# LineFollowerSensor.net
KiCad netlist of a schematic drawn in Altium Designer
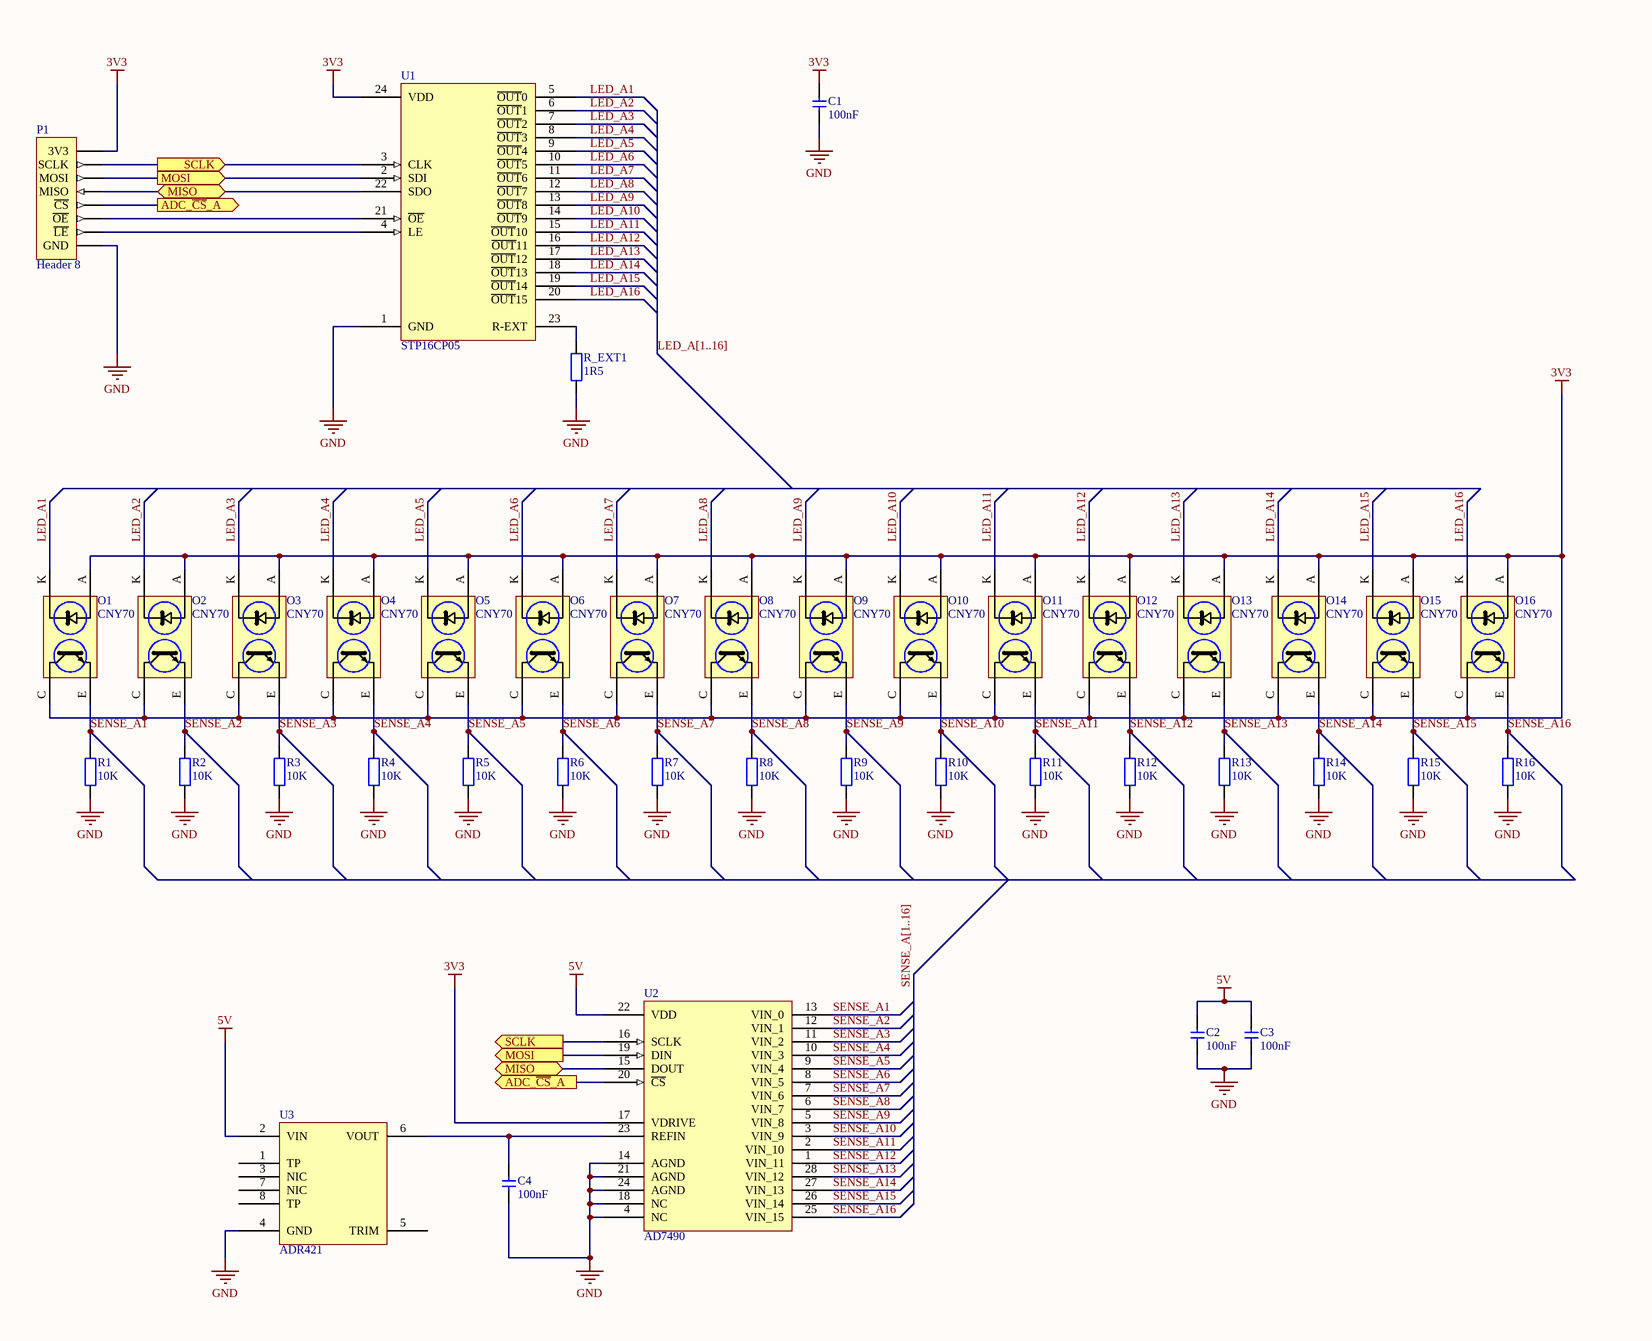
[diagram p0: LineFollowerSensor.SchDoc, left]
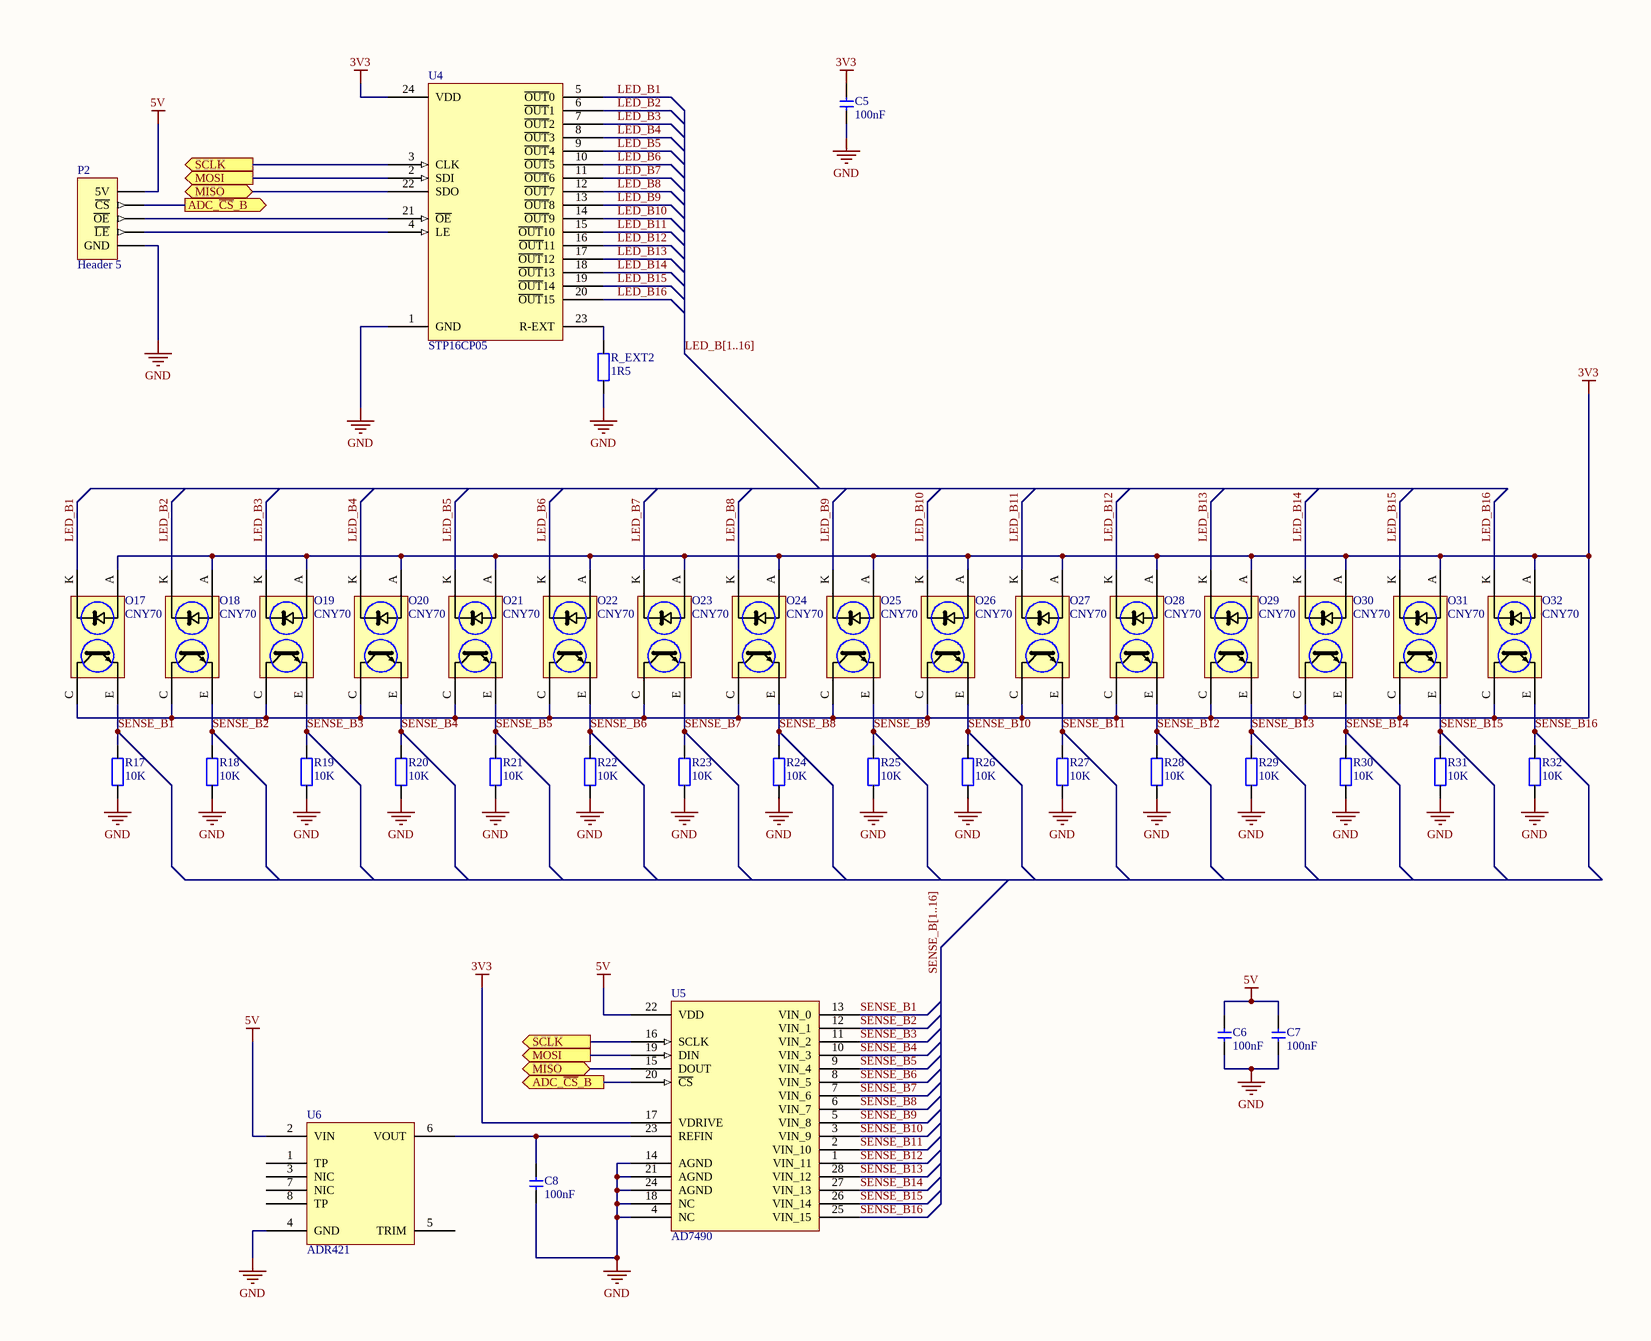
[diagram p1: LineFollowerSensor.SchDoc, right]

(export (version "E")
  (design (tool "Eeschema 10.0.6"))
  (components
    (comp (ref "C1")
      (value "100nF")
      (footprint "FP_0805_CAP_085")
      (description "YAGEO Ceramic Capacitor")
      (fields (field (name "VOLTAGE") "50") (field (name "TOLERANCE") "10%"))
      (libsource (lib "RET0805_RES-CAP_lib") (part "CAP_100nF"))
    )
    (comp (ref "C2")
      (value "100nF")
      (footprint "FP_0805_CAP_085")
      (description "YAGEO Ceramic Capacitor")
      (fields (field (name "VOLTAGE") "50") (field (name "TOLERANCE") "10%"))
      (libsource (lib "RET0805_RES-CAP_lib") (part "CAP_100nF"))
    )
    (comp (ref "C3")
      (value "100nF")
      (footprint "FP_0805_CAP_085")
      (description "YAGEO Ceramic Capacitor")
      (fields (field (name "VOLTAGE") "50") (field (name "TOLERANCE") "10%"))
      (libsource (lib "RET0805_RES-CAP_lib") (part "CAP_100nF"))
    )
    (comp (ref "C4")
      (value "100nF")
      (footprint "FP_0805_CAP_085")
      (description "YAGEO Ceramic Capacitor")
      (fields (field (name "VOLTAGE") "50") (field (name "TOLERANCE") "10%"))
      (libsource (lib "RET0805_RES-CAP_lib") (part "CAP_100nF"))
    )
    (comp (ref "C5")
      (value "100nF")
      (footprint "FP_0805_CAP_085")
      (description "YAGEO Ceramic Capacitor")
      (fields (field (name "VOLTAGE") "50") (field (name "TOLERANCE") "10%"))
      (libsource (lib "RET0805_RES-CAP_lib") (part "CAP_100nF"))
    )
    (comp (ref "C6")
      (value "100nF")
      (footprint "FP_0805_CAP_085")
      (description "YAGEO Ceramic Capacitor")
      (fields (field (name "VOLTAGE") "50") (field (name "TOLERANCE") "10%"))
      (libsource (lib "RET0805_RES-CAP_lib") (part "CAP_100nF"))
    )
    (comp (ref "C7")
      (value "100nF")
      (footprint "FP_0805_CAP_085")
      (description "YAGEO Ceramic Capacitor")
      (fields (field (name "VOLTAGE") "50") (field (name "TOLERANCE") "10%"))
      (libsource (lib "RET0805_RES-CAP_lib") (part "CAP_100nF"))
    )
    (comp (ref "C8")
      (value "100nF")
      (footprint "FP_0805_CAP_085")
      (description "YAGEO Ceramic Capacitor")
      (fields (field (name "VOLTAGE") "50") (field (name "TOLERANCE") "10%"))
      (libsource (lib "RET0805_RES-CAP_lib") (part "CAP_100nF"))
    )
    (comp (ref "O1")
      (value "CNY70")
      (footprint "FP_CNY70")
      (description "Optoérzékelő, CNY70")
      (libsource (lib "hallglib") (part "CNY70"))
    )
    (comp (ref "O2")
      (value "CNY70")
      (footprint "FP_CNY70")
      (description "Optoérzékelő, CNY70")
      (libsource (lib "hallglib") (part "CNY70"))
    )
    (comp (ref "O3")
      (value "CNY70")
      (footprint "FP_CNY70")
      (description "Optoérzékelő, CNY70")
      (libsource (lib "hallglib") (part "CNY70"))
    )
    (comp (ref "O4")
      (value "CNY70")
      (footprint "FP_CNY70")
      (description "Optoérzékelő, CNY70")
      (libsource (lib "hallglib") (part "CNY70"))
    )
    (comp (ref "O5")
      (value "CNY70")
      (footprint "FP_CNY70")
      (description "Optoérzékelő, CNY70")
      (libsource (lib "hallglib") (part "CNY70"))
    )
    (comp (ref "O6")
      (value "CNY70")
      (footprint "FP_CNY70")
      (description "Optoérzékelő, CNY70")
      (libsource (lib "hallglib") (part "CNY70"))
    )
    (comp (ref "O7")
      (value "CNY70")
      (footprint "FP_CNY70")
      (description "Optoérzékelő, CNY70")
      (libsource (lib "hallglib") (part "CNY70"))
    )
    (comp (ref "O8")
      (value "CNY70")
      (footprint "FP_CNY70")
      (description "Optoérzékelő, CNY70")
      (libsource (lib "hallglib") (part "CNY70"))
    )
    (comp (ref "O9")
      (value "CNY70")
      (footprint "FP_CNY70")
      (description "Optoérzékelő, CNY70")
      (libsource (lib "hallglib") (part "CNY70"))
    )
    (comp (ref "O10")
      (value "CNY70")
      (footprint "FP_CNY70")
      (description "Optoérzékelő, CNY70")
      (libsource (lib "hallglib") (part "CNY70"))
    )
    (comp (ref "O11")
      (value "CNY70")
      (footprint "FP_CNY70")
      (description "Optoérzékelő, CNY70")
      (libsource (lib "hallglib") (part "CNY70"))
    )
    (comp (ref "O12")
      (value "CNY70")
      (footprint "FP_CNY70")
      (description "Optoérzékelő, CNY70")
      (libsource (lib "hallglib") (part "CNY70"))
    )
    (comp (ref "O13")
      (value "CNY70")
      (footprint "FP_CNY70")
      (description "Optoérzékelő, CNY70")
      (libsource (lib "hallglib") (part "CNY70"))
    )
    (comp (ref "O14")
      (value "CNY70")
      (footprint "FP_CNY70")
      (description "Optoérzékelő, CNY70")
      (libsource (lib "hallglib") (part "CNY70"))
    )
    (comp (ref "O15")
      (value "CNY70")
      (footprint "FP_CNY70")
      (description "Optoérzékelő, CNY70")
      (libsource (lib "hallglib") (part "CNY70"))
    )
    (comp (ref "O16")
      (value "CNY70")
      (footprint "FP_CNY70")
      (description "Optoérzékelő, CNY70")
      (libsource (lib "hallglib") (part "CNY70"))
    )
    (comp (ref "O17")
      (value "CNY70")
      (footprint "FP_CNY70")
      (description "Optoérzékelő, CNY70")
      (libsource (lib "hallglib") (part "CNY70"))
    )
    (comp (ref "O18")
      (value "CNY70")
      (footprint "FP_CNY70")
      (description "Optoérzékelő, CNY70")
      (libsource (lib "hallglib") (part "CNY70"))
    )
    (comp (ref "O19")
      (value "CNY70")
      (footprint "FP_CNY70")
      (description "Optoérzékelő, CNY70")
      (libsource (lib "hallglib") (part "CNY70"))
    )
    (comp (ref "O20")
      (value "CNY70")
      (footprint "FP_CNY70")
      (description "Optoérzékelő, CNY70")
      (libsource (lib "hallglib") (part "CNY70"))
    )
    (comp (ref "O21")
      (value "CNY70")
      (footprint "FP_CNY70")
      (description "Optoérzékelő, CNY70")
      (libsource (lib "hallglib") (part "CNY70"))
    )
    (comp (ref "O22")
      (value "CNY70")
      (footprint "FP_CNY70")
      (description "Optoérzékelő, CNY70")
      (libsource (lib "hallglib") (part "CNY70"))
    )
    (comp (ref "O23")
      (value "CNY70")
      (footprint "FP_CNY70")
      (description "Optoérzékelő, CNY70")
      (libsource (lib "hallglib") (part "CNY70"))
    )
    (comp (ref "O24")
      (value "CNY70")
      (footprint "FP_CNY70")
      (description "Optoérzékelő, CNY70")
      (libsource (lib "hallglib") (part "CNY70"))
    )
    (comp (ref "O25")
      (value "CNY70")
      (footprint "FP_CNY70")
      (description "Optoérzékelő, CNY70")
      (libsource (lib "hallglib") (part "CNY70"))
    )
    (comp (ref "O26")
      (value "CNY70")
      (footprint "FP_CNY70")
      (description "Optoérzékelő, CNY70")
      (libsource (lib "hallglib") (part "CNY70"))
    )
    (comp (ref "O27")
      (value "CNY70")
      (footprint "FP_CNY70")
      (description "Optoérzékelő, CNY70")
      (libsource (lib "hallglib") (part "CNY70"))
    )
    (comp (ref "O28")
      (value "CNY70")
      (footprint "FP_CNY70")
      (description "Optoérzékelő, CNY70")
      (libsource (lib "hallglib") (part "CNY70"))
    )
    (comp (ref "O29")
      (value "CNY70")
      (footprint "FP_CNY70")
      (description "Optoérzékelő, CNY70")
      (libsource (lib "hallglib") (part "CNY70"))
    )
    (comp (ref "O30")
      (value "CNY70")
      (footprint "FP_CNY70")
      (description "Optoérzékelő, CNY70")
      (libsource (lib "hallglib") (part "CNY70"))
    )
    (comp (ref "O31")
      (value "CNY70")
      (footprint "FP_CNY70")
      (description "Optoérzékelő, CNY70")
      (libsource (lib "hallglib") (part "CNY70"))
    )
    (comp (ref "O32")
      (value "CNY70")
      (footprint "FP_CNY70")
      (description "Optoérzékelő, CNY70")
      (libsource (lib "hallglib") (part "CNY70"))
    )
    (comp (ref "P1")
      (value "Header 8")
      (footprint "HDR1X8")
      (description "Header, 8-Pin")
      (fields (field (name "PUBLISHER") "Altium Limited"))
      (libsource (lib "Miscellaneous Connectors") (part "Header 8"))
    )
    (comp (ref "P2")
      (value "Header 5")
      (footprint "HDR1X5")
      (description "Header, 5-Pin")
      (fields (field (name "PUBLISHER") "Altium Limited"))
      (libsource (lib "Miscellaneous Connectors") (part "Header 5"))
    )
    (comp (ref "R1")
      (value "10K")
      (footprint "FP_0805_RES")
      (description "YAGEO SMD RESISTOR")
      (fields (field (name "POWER") "125 mW") (field (name "TOLERANCE") "1%"))
      (libsource (lib "RET0805_RES-CAP_lib") (part "RES_10K"))
    )
    (comp (ref "R2")
      (value "10K")
      (footprint "FP_0805_RES")
      (description "YAGEO SMD RESISTOR")
      (fields (field (name "POWER") "125 mW") (field (name "TOLERANCE") "1%"))
      (libsource (lib "RET0805_RES-CAP_lib") (part "RES_10K"))
    )
    (comp (ref "R3")
      (value "10K")
      (footprint "FP_0805_RES")
      (description "YAGEO SMD RESISTOR")
      (fields (field (name "POWER") "125 mW") (field (name "TOLERANCE") "1%"))
      (libsource (lib "RET0805_RES-CAP_lib") (part "RES_10K"))
    )
    (comp (ref "R4")
      (value "10K")
      (footprint "FP_0805_RES")
      (description "YAGEO SMD RESISTOR")
      (fields (field (name "POWER") "125 mW") (field (name "TOLERANCE") "1%"))
      (libsource (lib "RET0805_RES-CAP_lib") (part "RES_10K"))
    )
    (comp (ref "R5")
      (value "10K")
      (footprint "FP_0805_RES")
      (description "YAGEO SMD RESISTOR")
      (fields (field (name "POWER") "125 mW") (field (name "TOLERANCE") "1%"))
      (libsource (lib "RET0805_RES-CAP_lib") (part "RES_10K"))
    )
    (comp (ref "R6")
      (value "10K")
      (footprint "FP_0805_RES")
      (description "YAGEO SMD RESISTOR")
      (fields (field (name "POWER") "125 mW") (field (name "TOLERANCE") "1%"))
      (libsource (lib "RET0805_RES-CAP_lib") (part "RES_10K"))
    )
    (comp (ref "R7")
      (value "10K")
      (footprint "FP_0805_RES")
      (description "YAGEO SMD RESISTOR")
      (fields (field (name "POWER") "125 mW") (field (name "TOLERANCE") "1%"))
      (libsource (lib "RET0805_RES-CAP_lib") (part "RES_10K"))
    )
    (comp (ref "R8")
      (value "10K")
      (footprint "FP_0805_RES")
      (description "YAGEO SMD RESISTOR")
      (fields (field (name "POWER") "125 mW") (field (name "TOLERANCE") "1%"))
      (libsource (lib "RET0805_RES-CAP_lib") (part "RES_10K"))
    )
    (comp (ref "R9")
      (value "10K")
      (footprint "FP_0805_RES")
      (description "YAGEO SMD RESISTOR")
      (fields (field (name "POWER") "125 mW") (field (name "TOLERANCE") "1%"))
      (libsource (lib "RET0805_RES-CAP_lib") (part "RES_10K"))
    )
    (comp (ref "R10")
      (value "10K")
      (footprint "FP_0805_RES")
      (description "YAGEO SMD RESISTOR")
      (fields (field (name "POWER") "125 mW") (field (name "TOLERANCE") "1%"))
      (libsource (lib "RET0805_RES-CAP_lib") (part "RES_10K"))
    )
    (comp (ref "R11")
      (value "10K")
      (footprint "FP_0805_RES")
      (description "YAGEO SMD RESISTOR")
      (fields (field (name "POWER") "125 mW") (field (name "TOLERANCE") "1%"))
      (libsource (lib "RET0805_RES-CAP_lib") (part "RES_10K"))
    )
    (comp (ref "R12")
      (value "10K")
      (footprint "FP_0805_RES")
      (description "YAGEO SMD RESISTOR")
      (fields (field (name "POWER") "125 mW") (field (name "TOLERANCE") "1%"))
      (libsource (lib "RET0805_RES-CAP_lib") (part "RES_10K"))
    )
    (comp (ref "R13")
      (value "10K")
      (footprint "FP_0805_RES")
      (description "YAGEO SMD RESISTOR")
      (fields (field (name "POWER") "125 mW") (field (name "TOLERANCE") "1%"))
      (libsource (lib "RET0805_RES-CAP_lib") (part "RES_10K"))
    )
    (comp (ref "R14")
      (value "10K")
      (footprint "FP_0805_RES")
      (description "YAGEO SMD RESISTOR")
      (fields (field (name "POWER") "125 mW") (field (name "TOLERANCE") "1%"))
      (libsource (lib "RET0805_RES-CAP_lib") (part "RES_10K"))
    )
    (comp (ref "R15")
      (value "10K")
      (footprint "FP_0805_RES")
      (description "YAGEO SMD RESISTOR")
      (fields (field (name "POWER") "125 mW") (field (name "TOLERANCE") "1%"))
      (libsource (lib "RET0805_RES-CAP_lib") (part "RES_10K"))
    )
    (comp (ref "R16")
      (value "10K")
      (footprint "FP_0805_RES")
      (description "YAGEO SMD RESISTOR")
      (fields (field (name "POWER") "125 mW") (field (name "TOLERANCE") "1%"))
      (libsource (lib "RET0805_RES-CAP_lib") (part "RES_10K"))
    )
    (comp (ref "R17")
      (value "10K")
      (footprint "FP_0805_RES")
      (description "YAGEO SMD RESISTOR")
      (fields (field (name "POWER") "125 mW") (field (name "TOLERANCE") "1%"))
      (libsource (lib "RET0805_RES-CAP_lib") (part "RES_10K"))
    )
    (comp (ref "R18")
      (value "10K")
      (footprint "FP_0805_RES")
      (description "YAGEO SMD RESISTOR")
      (fields (field (name "POWER") "125 mW") (field (name "TOLERANCE") "1%"))
      (libsource (lib "RET0805_RES-CAP_lib") (part "RES_10K"))
    )
    (comp (ref "R19")
      (value "10K")
      (footprint "FP_0805_RES")
      (description "YAGEO SMD RESISTOR")
      (fields (field (name "POWER") "125 mW") (field (name "TOLERANCE") "1%"))
      (libsource (lib "RET0805_RES-CAP_lib") (part "RES_10K"))
    )
    (comp (ref "R20")
      (value "10K")
      (footprint "FP_0805_RES")
      (description "YAGEO SMD RESISTOR")
      (fields (field (name "POWER") "125 mW") (field (name "TOLERANCE") "1%"))
      (libsource (lib "RET0805_RES-CAP_lib") (part "RES_10K"))
    )
    (comp (ref "R21")
      (value "10K")
      (footprint "FP_0805_RES")
      (description "YAGEO SMD RESISTOR")
      (fields (field (name "POWER") "125 mW") (field (name "TOLERANCE") "1%"))
      (libsource (lib "RET0805_RES-CAP_lib") (part "RES_10K"))
    )
    (comp (ref "R22")
      (value "10K")
      (footprint "FP_0805_RES")
      (description "YAGEO SMD RESISTOR")
      (fields (field (name "POWER") "125 mW") (field (name "TOLERANCE") "1%"))
      (libsource (lib "RET0805_RES-CAP_lib") (part "RES_10K"))
    )
    (comp (ref "R23")
      (value "10K")
      (footprint "FP_0805_RES")
      (description "YAGEO SMD RESISTOR")
      (fields (field (name "POWER") "125 mW") (field (name "TOLERANCE") "1%"))
      (libsource (lib "RET0805_RES-CAP_lib") (part "RES_10K"))
    )
    (comp (ref "R24")
      (value "10K")
      (footprint "FP_0805_RES")
      (description "YAGEO SMD RESISTOR")
      (fields (field (name "POWER") "125 mW") (field (name "TOLERANCE") "1%"))
      (libsource (lib "RET0805_RES-CAP_lib") (part "RES_10K"))
    )
    (comp (ref "R25")
      (value "10K")
      (footprint "FP_0805_RES")
      (description "YAGEO SMD RESISTOR")
      (fields (field (name "POWER") "125 mW") (field (name "TOLERANCE") "1%"))
      (libsource (lib "RET0805_RES-CAP_lib") (part "RES_10K"))
    )
    (comp (ref "R26")
      (value "10K")
      (footprint "FP_0805_RES")
      (description "YAGEO SMD RESISTOR")
      (fields (field (name "POWER") "125 mW") (field (name "TOLERANCE") "1%"))
      (libsource (lib "RET0805_RES-CAP_lib") (part "RES_10K"))
    )
    (comp (ref "R27")
      (value "10K")
      (footprint "FP_0805_RES")
      (description "YAGEO SMD RESISTOR")
      (fields (field (name "POWER") "125 mW") (field (name "TOLERANCE") "1%"))
      (libsource (lib "RET0805_RES-CAP_lib") (part "RES_10K"))
    )
    (comp (ref "R28")
      (value "10K")
      (footprint "FP_0805_RES")
      (description "YAGEO SMD RESISTOR")
      (fields (field (name "POWER") "125 mW") (field (name "TOLERANCE") "1%"))
      (libsource (lib "RET0805_RES-CAP_lib") (part "RES_10K"))
    )
    (comp (ref "R29")
      (value "10K")
      (footprint "FP_0805_RES")
      (description "YAGEO SMD RESISTOR")
      (fields (field (name "POWER") "125 mW") (field (name "TOLERANCE") "1%"))
      (libsource (lib "RET0805_RES-CAP_lib") (part "RES_10K"))
    )
    (comp (ref "R30")
      (value "10K")
      (footprint "FP_0805_RES")
      (description "YAGEO SMD RESISTOR")
      (fields (field (name "POWER") "125 mW") (field (name "TOLERANCE") "1%"))
      (libsource (lib "RET0805_RES-CAP_lib") (part "RES_10K"))
    )
    (comp (ref "R31")
      (value "10K")
      (footprint "FP_0805_RES")
      (description "YAGEO SMD RESISTOR")
      (fields (field (name "POWER") "125 mW") (field (name "TOLERANCE") "1%"))
      (libsource (lib "RET0805_RES-CAP_lib") (part "RES_10K"))
    )
    (comp (ref "R32")
      (value "10K")
      (footprint "FP_0805_RES")
      (description "YAGEO SMD RESISTOR")
      (fields (field (name "POWER") "125 mW") (field (name "TOLERANCE") "1%"))
      (libsource (lib "RET0805_RES-CAP_lib") (part "RES_10K"))
    )
    (comp (ref "R_EXT1")
      (value "1R5")
      (footprint "FP_0805_RES")
      (description "YAGEO SMD RESISTOR")
      (fields (field (name "POWER") "125 mW") (field (name "TOLERANCE") "1%"))
      (libsource (lib "RET0805_RES-CAP_lib") (part "RES_1R5"))
    )
    (comp (ref "R_EXT2")
      (value "1R5")
      (footprint "FP_0805_RES")
      (description "YAGEO SMD RESISTOR")
      (fields (field (name "POWER") "125 mW") (field (name "TOLERANCE") "1%"))
      (libsource (lib "RET0805_RES-CAP_lib") (part "RES_1R5"))
    )
    (comp (ref "U1")
      (value "STP16CP05")
      (footprint "TSSOP24")
      (description "16 channel constant current LED driver")
      (libsource (lib "LineFollowerSensor") (part "STP16CP05"))
    )
    (comp (ref "U2")
      (value "AD7490")
      (footprint "TSSOP28")
      (description "16 channel analog digital converter")
      (libsource (lib "LineFollowerSensor") (part "AD7490"))
    )
    (comp (ref "U3")
      (value "ADR421")
      (footprint "SOIC8")
      (description "Reference voltage generator")
      (libsource (lib "LineFollowerSensor") (part "ADR421"))
    )
    (comp (ref "U4")
      (value "STP16CP05")
      (footprint "TSSOP24")
      (description "16 channel constant current LED driver")
      (libsource (lib "LineFollowerSensor") (part "STP16CP05"))
    )
    (comp (ref "U5")
      (value "AD7490")
      (footprint "TSSOP28")
      (description "16 channel analog digital converter")
      (libsource (lib "LineFollowerSensor") (part "AD7490"))
    )
    (comp (ref "U6")
      (value "ADR421")
      (footprint "SOIC8")
      (description "Reference voltage generator")
      (libsource (lib "LineFollowerSensor") (part "ADR421"))
    )
  )
  (nets
    (net (code "1") (name "/ADC_~{CS}_A") (class "Default")
      (node (ref "P1") (pin "5") (pinfunction "~{CS}_5") (pintype "output"))
      (node (ref "U2") (pin "20") (pinfunction "~{CS}_20") (pintype "input"))
    )
    (net (code "2") (name "/ADC_~{CS}_B") (class "Default")
      (node (ref "P2") (pin "2") (pinfunction "~{CS}_2") (pintype "output"))
      (node (ref "U5") (pin "20") (pinfunction "~{CS}_20") (pintype "input"))
    )
    (net (code "3") (name "/LED_A1") (class "Default")
      (node (ref "O1") (pin "K") (pinfunction "Cath_K") (pintype "passive"))
      (node (ref "U1") (pin "5") (pinfunction "~{OUT}0_5") (pintype "open_collector"))
    )
    (net (code "4") (name "/LED_A2") (class "Default")
      (node (ref "O2") (pin "K") (pinfunction "Cath_K") (pintype "passive"))
      (node (ref "U1") (pin "6") (pinfunction "~{OUT}1_6") (pintype "open_collector"))
    )
    (net (code "5") (name "/LED_A3") (class "Default")
      (node (ref "O3") (pin "K") (pinfunction "Cath_K") (pintype "passive"))
      (node (ref "U1") (pin "7") (pinfunction "~{OUT}2_7") (pintype "open_collector"))
    )
    (net (code "6") (name "/LED_A4") (class "Default")
      (node (ref "O4") (pin "K") (pinfunction "Cath_K") (pintype "passive"))
      (node (ref "U1") (pin "8") (pinfunction "~{OUT}3_8") (pintype "open_collector"))
    )
    (net (code "7") (name "/LED_A5") (class "Default")
      (node (ref "O5") (pin "K") (pinfunction "Cath_K") (pintype "passive"))
      (node (ref "U1") (pin "9") (pinfunction "~{OUT}4_9") (pintype "open_collector"))
    )
    (net (code "8") (name "/LED_A6") (class "Default")
      (node (ref "O6") (pin "K") (pinfunction "Cath_K") (pintype "passive"))
      (node (ref "U1") (pin "10") (pinfunction "~{OUT}5_10") (pintype "open_collector"))
    )
    (net (code "9") (name "/LED_A7") (class "Default")
      (node (ref "O7") (pin "K") (pinfunction "Cath_K") (pintype "passive"))
      (node (ref "U1") (pin "11") (pinfunction "~{OUT}6_11") (pintype "open_collector"))
    )
    (net (code "10") (name "/LED_A8") (class "Default")
      (node (ref "O8") (pin "K") (pinfunction "Cath_K") (pintype "passive"))
      (node (ref "U1") (pin "12") (pinfunction "~{OUT}7_12") (pintype "open_collector"))
    )
    (net (code "11") (name "/LED_A9") (class "Default")
      (node (ref "O9") (pin "K") (pinfunction "Cath_K") (pintype "passive"))
      (node (ref "U1") (pin "13") (pinfunction "~{OUT}8_13") (pintype "open_collector"))
    )
    (net (code "12") (name "/LED_A10") (class "Default")
      (node (ref "O10") (pin "K") (pinfunction "Cath_K") (pintype "passive"))
      (node (ref "U1") (pin "14") (pinfunction "~{OUT}9_14") (pintype "open_collector"))
    )
    (net (code "13") (name "/LED_A11") (class "Default")
      (node (ref "O11") (pin "K") (pinfunction "Cath_K") (pintype "passive"))
      (node (ref "U1") (pin "15") (pinfunction "~{OUT}10_15") (pintype "open_collector"))
    )
    (net (code "14") (name "/LED_A12") (class "Default")
      (node (ref "O12") (pin "K") (pinfunction "Cath_K") (pintype "passive"))
      (node (ref "U1") (pin "16") (pinfunction "~{OUT}11_16") (pintype "open_collector"))
    )
    (net (code "15") (name "/LED_A13") (class "Default")
      (node (ref "O13") (pin "K") (pinfunction "Cath_K") (pintype "passive"))
      (node (ref "U1") (pin "17") (pinfunction "~{OUT}12_17") (pintype "open_collector"))
    )
    (net (code "16") (name "/LED_A14") (class "Default")
      (node (ref "O14") (pin "K") (pinfunction "Cath_K") (pintype "passive"))
      (node (ref "U1") (pin "18") (pinfunction "~{OUT}13_18") (pintype "open_collector"))
    )
    (net (code "17") (name "/LED_A15") (class "Default")
      (node (ref "O15") (pin "K") (pinfunction "Cath_K") (pintype "passive"))
      (node (ref "U1") (pin "19") (pinfunction "~{OUT}14_19") (pintype "open_collector"))
    )
    (net (code "18") (name "/LED_A16") (class "Default")
      (node (ref "O16") (pin "K") (pinfunction "Cath_K") (pintype "passive"))
      (node (ref "U1") (pin "20") (pinfunction "~{OUT}15_20") (pintype "open_collector"))
    )
    (net (code "20") (name "/LED_B1") (class "Default")
      (node (ref "O17") (pin "K") (pinfunction "Cath_K") (pintype "passive"))
      (node (ref "U4") (pin "5") (pinfunction "~{OUT}0_5") (pintype "open_collector"))
    )
    (net (code "21") (name "/LED_B2") (class "Default")
      (node (ref "O18") (pin "K") (pinfunction "Cath_K") (pintype "passive"))
      (node (ref "U4") (pin "6") (pinfunction "~{OUT}1_6") (pintype "open_collector"))
    )
    (net (code "22") (name "/LED_B3") (class "Default")
      (node (ref "O19") (pin "K") (pinfunction "Cath_K") (pintype "passive"))
      (node (ref "U4") (pin "7") (pinfunction "~{OUT}2_7") (pintype "open_collector"))
    )
    (net (code "23") (name "/LED_B4") (class "Default")
      (node (ref "O20") (pin "K") (pinfunction "Cath_K") (pintype "passive"))
      (node (ref "U4") (pin "8") (pinfunction "~{OUT}3_8") (pintype "open_collector"))
    )
    (net (code "24") (name "/LED_B5") (class "Default")
      (node (ref "O21") (pin "K") (pinfunction "Cath_K") (pintype "passive"))
      (node (ref "U4") (pin "9") (pinfunction "~{OUT}4_9") (pintype "open_collector"))
    )
    (net (code "25") (name "/LED_B6") (class "Default")
      (node (ref "O22") (pin "K") (pinfunction "Cath_K") (pintype "passive"))
      (node (ref "U4") (pin "10") (pinfunction "~{OUT}5_10") (pintype "open_collector"))
    )
    (net (code "26") (name "/LED_B7") (class "Default")
      (node (ref "O23") (pin "K") (pinfunction "Cath_K") (pintype "passive"))
      (node (ref "U4") (pin "11") (pinfunction "~{OUT}6_11") (pintype "open_collector"))
    )
    (net (code "27") (name "/LED_B8") (class "Default")
      (node (ref "O24") (pin "K") (pinfunction "Cath_K") (pintype "passive"))
      (node (ref "U4") (pin "12") (pinfunction "~{OUT}7_12") (pintype "open_collector"))
    )
    (net (code "28") (name "/LED_B9") (class "Default")
      (node (ref "O25") (pin "K") (pinfunction "Cath_K") (pintype "passive"))
      (node (ref "U4") (pin "13") (pinfunction "~{OUT}8_13") (pintype "open_collector"))
    )
    (net (code "29") (name "/LED_B10") (class "Default")
      (node (ref "O26") (pin "K") (pinfunction "Cath_K") (pintype "passive"))
      (node (ref "U4") (pin "14") (pinfunction "~{OUT}9_14") (pintype "open_collector"))
    )
    (net (code "30") (name "/LED_B11") (class "Default")
      (node (ref "O27") (pin "K") (pinfunction "Cath_K") (pintype "passive"))
      (node (ref "U4") (pin "15") (pinfunction "~{OUT}10_15") (pintype "open_collector"))
    )
    (net (code "31") (name "/LED_B12") (class "Default")
      (node (ref "O28") (pin "K") (pinfunction "Cath_K") (pintype "passive"))
      (node (ref "U4") (pin "16") (pinfunction "~{OUT}11_16") (pintype "open_collector"))
    )
    (net (code "32") (name "/LED_B13") (class "Default")
      (node (ref "O29") (pin "K") (pinfunction "Cath_K") (pintype "passive"))
      (node (ref "U4") (pin "17") (pinfunction "~{OUT}12_17") (pintype "open_collector"))
    )
    (net (code "33") (name "/LED_B14") (class "Default")
      (node (ref "O30") (pin "K") (pinfunction "Cath_K") (pintype "passive"))
      (node (ref "U4") (pin "18") (pinfunction "~{OUT}13_18") (pintype "open_collector"))
    )
    (net (code "34") (name "/LED_B15") (class "Default")
      (node (ref "O31") (pin "K") (pinfunction "Cath_K") (pintype "passive"))
      (node (ref "U4") (pin "19") (pinfunction "~{OUT}14_19") (pintype "open_collector"))
    )
    (net (code "35") (name "/LED_B16") (class "Default")
      (node (ref "O32") (pin "K") (pinfunction "Cath_K") (pintype "passive"))
      (node (ref "U4") (pin "20") (pinfunction "~{OUT}15_20") (pintype "open_collector"))
    )
    (net (code "37") (name "/MISO") (class "Default")
      (node (ref "P1") (pin "4") (pinfunction "MISO_4") (pintype "input"))
      (node (ref "U1") (pin "22") (pinfunction "SDO_22") (pintype "open_collector"))
      (node (ref "U2") (pin "15") (pinfunction "DOUT_15") (pintype "open_collector"))
      (node (ref "U4") (pin "22") (pinfunction "SDO_22") (pintype "open_collector"))
      (node (ref "U5") (pin "15") (pinfunction "DOUT_15") (pintype "open_collector"))
    )
    (net (code "38") (name "/MOSI") (class "Default")
      (node (ref "P1") (pin "3") (pinfunction "MOSI_3") (pintype "output"))
      (node (ref "U1") (pin "2") (pinfunction "SDI_2") (pintype "input"))
      (node (ref "U2") (pin "19") (pinfunction "DIN_19") (pintype "input"))
      (node (ref "U4") (pin "2") (pinfunction "SDI_2") (pintype "input"))
      (node (ref "U5") (pin "19") (pinfunction "DIN_19") (pintype "input"))
    )
    (net (code "39") (name "/SCLK") (class "Default")
      (node (ref "P1") (pin "2") (pinfunction "SCLK_2") (pintype "output"))
      (node (ref "U1") (pin "3") (pinfunction "CLK_3") (pintype "input"))
      (node (ref "U2") (pin "16") (pinfunction "SCLK_16") (pintype "input"))
      (node (ref "U4") (pin "3") (pinfunction "CLK_3") (pintype "input"))
      (node (ref "U5") (pin "16") (pinfunction "SCLK_16") (pintype "input"))
    )
    (net (code "40") (name "/SENSE_A1") (class "Default")
      (node (ref "O1") (pin "E") (pinfunction "Em_E") (pintype "passive"))
      (node (ref "R1") (pin "1") (pinfunction "1_1") (pintype "passive"))
      (node (ref "U2") (pin "13") (pinfunction "VIN_0_13") (pintype "passive"))
    )
    (net (code "41") (name "/SENSE_A2") (class "Default")
      (node (ref "O2") (pin "E") (pinfunction "Em_E") (pintype "passive"))
      (node (ref "R2") (pin "2") (pinfunction "2_2") (pintype "passive"))
      (node (ref "U2") (pin "12") (pinfunction "VIN_1_12") (pintype "passive"))
    )
    (net (code "42") (name "/SENSE_A3") (class "Default")
      (node (ref "O3") (pin "E") (pinfunction "Em_E") (pintype "passive"))
      (node (ref "R3") (pin "2") (pinfunction "2_2") (pintype "passive"))
      (node (ref "U2") (pin "11") (pinfunction "VIN_2_11") (pintype "passive"))
    )
    (net (code "43") (name "/SENSE_A4") (class "Default")
      (node (ref "O4") (pin "E") (pinfunction "Em_E") (pintype "passive"))
      (node (ref "R4") (pin "2") (pinfunction "2_2") (pintype "passive"))
      (node (ref "U2") (pin "10") (pinfunction "VIN_3_10") (pintype "passive"))
    )
    (net (code "44") (name "/SENSE_A5") (class "Default")
      (node (ref "O5") (pin "E") (pinfunction "Em_E") (pintype "passive"))
      (node (ref "R5") (pin "2") (pinfunction "2_2") (pintype "passive"))
      (node (ref "U2") (pin "9") (pinfunction "VIN_4_9") (pintype "passive"))
    )
    (net (code "45") (name "/SENSE_A6") (class "Default")
      (node (ref "O6") (pin "E") (pinfunction "Em_E") (pintype "passive"))
      (node (ref "R6") (pin "2") (pinfunction "2_2") (pintype "passive"))
      (node (ref "U2") (pin "8") (pinfunction "VIN_5_8") (pintype "passive"))
    )
    (net (code "46") (name "/SENSE_A7") (class "Default")
      (node (ref "O7") (pin "E") (pinfunction "Em_E") (pintype "passive"))
      (node (ref "R7") (pin "2") (pinfunction "2_2") (pintype "passive"))
      (node (ref "U2") (pin "7") (pinfunction "VIN_6_7") (pintype "passive"))
    )
    (net (code "47") (name "/SENSE_A8") (class "Default")
      (node (ref "O8") (pin "E") (pinfunction "Em_E") (pintype "passive"))
      (node (ref "R8") (pin "2") (pinfunction "2_2") (pintype "passive"))
      (node (ref "U2") (pin "6") (pinfunction "VIN_7_6") (pintype "passive"))
    )
    (net (code "48") (name "/SENSE_A9") (class "Default")
      (node (ref "O9") (pin "E") (pinfunction "Em_E") (pintype "passive"))
      (node (ref "R9") (pin "2") (pinfunction "2_2") (pintype "passive"))
      (node (ref "U2") (pin "5") (pinfunction "VIN_8_5") (pintype "passive"))
    )
    (net (code "49") (name "/SENSE_A10") (class "Default")
      (node (ref "O10") (pin "E") (pinfunction "Em_E") (pintype "passive"))
      (node (ref "R10") (pin "2") (pinfunction "2_2") (pintype "passive"))
      (node (ref "U2") (pin "3") (pinfunction "VIN_9_3") (pintype "passive"))
    )
    (net (code "50") (name "/SENSE_A11") (class "Default")
      (node (ref "O11") (pin "E") (pinfunction "Em_E") (pintype "passive"))
      (node (ref "R11") (pin "2") (pinfunction "2_2") (pintype "passive"))
      (node (ref "U2") (pin "2") (pinfunction "VIN_10_2") (pintype "passive"))
    )
    (net (code "51") (name "/SENSE_A12") (class "Default")
      (node (ref "O12") (pin "E") (pinfunction "Em_E") (pintype "passive"))
      (node (ref "R12") (pin "2") (pinfunction "2_2") (pintype "passive"))
      (node (ref "U2") (pin "1") (pinfunction "VIN_11_1") (pintype "passive"))
    )
    (net (code "52") (name "/SENSE_A13") (class "Default")
      (node (ref "O13") (pin "E") (pinfunction "Em_E") (pintype "passive"))
      (node (ref "R13") (pin "2") (pinfunction "2_2") (pintype "passive"))
      (node (ref "U2") (pin "28") (pinfunction "VIN_12_28") (pintype "power_in"))
    )
    (net (code "53") (name "/SENSE_A14") (class "Default")
      (node (ref "O14") (pin "E") (pinfunction "Em_E") (pintype "passive"))
      (node (ref "R14") (pin "2") (pinfunction "2_2") (pintype "passive"))
      (node (ref "U2") (pin "27") (pinfunction "VIN_13_27") (pintype "power_in"))
    )
    (net (code "54") (name "/SENSE_A15") (class "Default")
      (node (ref "O15") (pin "E") (pinfunction "Em_E") (pintype "passive"))
      (node (ref "R15") (pin "2") (pinfunction "2_2") (pintype "passive"))
      (node (ref "U2") (pin "26") (pinfunction "VIN_14_26") (pintype "power_in"))
    )
    (net (code "55") (name "/SENSE_A16") (class "Default")
      (node (ref "O16") (pin "E") (pinfunction "Em_E") (pintype "passive"))
      (node (ref "R16") (pin "2") (pinfunction "2_2") (pintype "passive"))
      (node (ref "U2") (pin "25") (pinfunction "VIN_15_25") (pintype "power_in"))
    )
    (net (code "57") (name "/SENSE_B1") (class "Default")
      (node (ref "O17") (pin "E") (pinfunction "Em_E") (pintype "passive"))
      (node (ref "R17") (pin "1") (pinfunction "1_1") (pintype "passive"))
      (node (ref "U5") (pin "13") (pinfunction "VIN_0_13") (pintype "passive"))
    )
    (net (code "58") (name "/SENSE_B2") (class "Default")
      (node (ref "O18") (pin "E") (pinfunction "Em_E") (pintype "passive"))
      (node (ref "R18") (pin "2") (pinfunction "2_2") (pintype "passive"))
      (node (ref "U5") (pin "12") (pinfunction "VIN_1_12") (pintype "passive"))
    )
    (net (code "59") (name "/SENSE_B3") (class "Default")
      (node (ref "O19") (pin "E") (pinfunction "Em_E") (pintype "passive"))
      (node (ref "R19") (pin "2") (pinfunction "2_2") (pintype "passive"))
      (node (ref "U5") (pin "11") (pinfunction "VIN_2_11") (pintype "passive"))
    )
    (net (code "60") (name "/SENSE_B4") (class "Default")
      (node (ref "O20") (pin "E") (pinfunction "Em_E") (pintype "passive"))
      (node (ref "R20") (pin "2") (pinfunction "2_2") (pintype "passive"))
      (node (ref "U5") (pin "10") (pinfunction "VIN_3_10") (pintype "passive"))
    )
    (net (code "61") (name "/SENSE_B5") (class "Default")
      (node (ref "O21") (pin "E") (pinfunction "Em_E") (pintype "passive"))
      (node (ref "R21") (pin "2") (pinfunction "2_2") (pintype "passive"))
      (node (ref "U5") (pin "9") (pinfunction "VIN_4_9") (pintype "passive"))
    )
    (net (code "62") (name "/SENSE_B6") (class "Default")
      (node (ref "O22") (pin "E") (pinfunction "Em_E") (pintype "passive"))
      (node (ref "R22") (pin "2") (pinfunction "2_2") (pintype "passive"))
      (node (ref "U5") (pin "8") (pinfunction "VIN_5_8") (pintype "passive"))
    )
    (net (code "63") (name "/SENSE_B7") (class "Default")
      (node (ref "O23") (pin "E") (pinfunction "Em_E") (pintype "passive"))
      (node (ref "R23") (pin "2") (pinfunction "2_2") (pintype "passive"))
      (node (ref "U5") (pin "7") (pinfunction "VIN_6_7") (pintype "passive"))
    )
    (net (code "64") (name "/SENSE_B8") (class "Default")
      (node (ref "O24") (pin "E") (pinfunction "Em_E") (pintype "passive"))
      (node (ref "R24") (pin "2") (pinfunction "2_2") (pintype "passive"))
      (node (ref "U5") (pin "6") (pinfunction "VIN_7_6") (pintype "passive"))
    )
    (net (code "65") (name "/SENSE_B9") (class "Default")
      (node (ref "O25") (pin "E") (pinfunction "Em_E") (pintype "passive"))
      (node (ref "R25") (pin "2") (pinfunction "2_2") (pintype "passive"))
      (node (ref "U5") (pin "5") (pinfunction "VIN_8_5") (pintype "passive"))
    )
    (net (code "66") (name "/SENSE_B10") (class "Default")
      (node (ref "O26") (pin "E") (pinfunction "Em_E") (pintype "passive"))
      (node (ref "R26") (pin "2") (pinfunction "2_2") (pintype "passive"))
      (node (ref "U5") (pin "3") (pinfunction "VIN_9_3") (pintype "passive"))
    )
    (net (code "67") (name "/SENSE_B11") (class "Default")
      (node (ref "O27") (pin "E") (pinfunction "Em_E") (pintype "passive"))
      (node (ref "R27") (pin "2") (pinfunction "2_2") (pintype "passive"))
      (node (ref "U5") (pin "2") (pinfunction "VIN_10_2") (pintype "passive"))
    )
    (net (code "68") (name "/SENSE_B12") (class "Default")
      (node (ref "O28") (pin "E") (pinfunction "Em_E") (pintype "passive"))
      (node (ref "R28") (pin "2") (pinfunction "2_2") (pintype "passive"))
      (node (ref "U5") (pin "1") (pinfunction "VIN_11_1") (pintype "passive"))
    )
    (net (code "69") (name "/SENSE_B13") (class "Default")
      (node (ref "O29") (pin "E") (pinfunction "Em_E") (pintype "passive"))
      (node (ref "R29") (pin "2") (pinfunction "2_2") (pintype "passive"))
      (node (ref "U5") (pin "28") (pinfunction "VIN_12_28") (pintype "power_in"))
    )
    (net (code "70") (name "/SENSE_B14") (class "Default")
      (node (ref "O30") (pin "E") (pinfunction "Em_E") (pintype "passive"))
      (node (ref "R30") (pin "2") (pinfunction "2_2") (pintype "passive"))
      (node (ref "U5") (pin "27") (pinfunction "VIN_13_27") (pintype "power_in"))
    )
    (net (code "71") (name "/SENSE_B15") (class "Default")
      (node (ref "O31") (pin "E") (pinfunction "Em_E") (pintype "passive"))
      (node (ref "R31") (pin "2") (pinfunction "2_2") (pintype "passive"))
      (node (ref "U5") (pin "26") (pinfunction "VIN_14_26") (pintype "power_in"))
    )
    (net (code "72") (name "/SENSE_B16") (class "Default")
      (node (ref "O32") (pin "E") (pinfunction "Em_E") (pintype "passive"))
      (node (ref "R32") (pin "2") (pinfunction "2_2") (pintype "passive"))
      (node (ref "U5") (pin "25") (pinfunction "VIN_15_25") (pintype "power_in"))
    )
    (net (code "74") (name "3V3") (class "Default")
      (node (ref "C1") (pin "2") (pinfunction "2_2") (pintype "passive"))
      (node (ref "C5") (pin "2") (pinfunction "2_2") (pintype "passive"))
      (node (ref "O1") (pin "A") (pinfunction "Anode_A") (pintype "passive"))
      (node (ref "O1") (pin "C") (pinfunction "Coll_C") (pintype "passive"))
      (node (ref "O10") (pin "A") (pinfunction "Anode_A") (pintype "passive"))
      (node (ref "O10") (pin "C") (pinfunction "Coll_C") (pintype "passive"))
      (node (ref "O11") (pin "A") (pinfunction "Anode_A") (pintype "passive"))
      (node (ref "O11") (pin "C") (pinfunction "Coll_C") (pintype "passive"))
      (node (ref "O12") (pin "A") (pinfunction "Anode_A") (pintype "passive"))
      (node (ref "O12") (pin "C") (pinfunction "Coll_C") (pintype "passive"))
      (node (ref "O13") (pin "A") (pinfunction "Anode_A") (pintype "passive"))
      (node (ref "O13") (pin "C") (pinfunction "Coll_C") (pintype "passive"))
      (node (ref "O14") (pin "A") (pinfunction "Anode_A") (pintype "passive"))
      (node (ref "O14") (pin "C") (pinfunction "Coll_C") (pintype "passive"))
      (node (ref "O15") (pin "A") (pinfunction "Anode_A") (pintype "passive"))
      (node (ref "O15") (pin "C") (pinfunction "Coll_C") (pintype "passive"))
      (node (ref "O16") (pin "A") (pinfunction "Anode_A") (pintype "passive"))
      (node (ref "O16") (pin "C") (pinfunction "Coll_C") (pintype "passive"))
      (node (ref "O17") (pin "A") (pinfunction "Anode_A") (pintype "passive"))
      (node (ref "O17") (pin "C") (pinfunction "Coll_C") (pintype "passive"))
      (node (ref "O18") (pin "A") (pinfunction "Anode_A") (pintype "passive"))
      (node (ref "O18") (pin "C") (pinfunction "Coll_C") (pintype "passive"))
      (node (ref "O19") (pin "A") (pinfunction "Anode_A") (pintype "passive"))
      (node (ref "O19") (pin "C") (pinfunction "Coll_C") (pintype "passive"))
      (node (ref "O2") (pin "A") (pinfunction "Anode_A") (pintype "passive"))
      (node (ref "O2") (pin "C") (pinfunction "Coll_C") (pintype "passive"))
      (node (ref "O20") (pin "A") (pinfunction "Anode_A") (pintype "passive"))
      (node (ref "O20") (pin "C") (pinfunction "Coll_C") (pintype "passive"))
      (node (ref "O21") (pin "A") (pinfunction "Anode_A") (pintype "passive"))
      (node (ref "O21") (pin "C") (pinfunction "Coll_C") (pintype "passive"))
      (node (ref "O22") (pin "A") (pinfunction "Anode_A") (pintype "passive"))
      (node (ref "O22") (pin "C") (pinfunction "Coll_C") (pintype "passive"))
      (node (ref "O23") (pin "A") (pinfunction "Anode_A") (pintype "passive"))
      (node (ref "O23") (pin "C") (pinfunction "Coll_C") (pintype "passive"))
      (node (ref "O24") (pin "A") (pinfunction "Anode_A") (pintype "passive"))
      (node (ref "O24") (pin "C") (pinfunction "Coll_C") (pintype "passive"))
      (node (ref "O25") (pin "A") (pinfunction "Anode_A") (pintype "passive"))
      (node (ref "O25") (pin "C") (pinfunction "Coll_C") (pintype "passive"))
      (node (ref "O26") (pin "A") (pinfunction "Anode_A") (pintype "passive"))
      (node (ref "O26") (pin "C") (pinfunction "Coll_C") (pintype "passive"))
      (node (ref "O27") (pin "A") (pinfunction "Anode_A") (pintype "passive"))
      (node (ref "O27") (pin "C") (pinfunction "Coll_C") (pintype "passive"))
      (node (ref "O28") (pin "A") (pinfunction "Anode_A") (pintype "passive"))
      (node (ref "O28") (pin "C") (pinfunction "Coll_C") (pintype "passive"))
      (node (ref "O29") (pin "A") (pinfunction "Anode_A") (pintype "passive"))
      (node (ref "O29") (pin "C") (pinfunction "Coll_C") (pintype "passive"))
      (node (ref "O3") (pin "A") (pinfunction "Anode_A") (pintype "passive"))
      (node (ref "O3") (pin "C") (pinfunction "Coll_C") (pintype "passive"))
      (node (ref "O30") (pin "A") (pinfunction "Anode_A") (pintype "passive"))
      (node (ref "O30") (pin "C") (pinfunction "Coll_C") (pintype "passive"))
      (node (ref "O31") (pin "A") (pinfunction "Anode_A") (pintype "passive"))
      (node (ref "O31") (pin "C") (pinfunction "Coll_C") (pintype "passive"))
      (node (ref "O32") (pin "A") (pinfunction "Anode_A") (pintype "passive"))
      (node (ref "O32") (pin "C") (pinfunction "Coll_C") (pintype "passive"))
      (node (ref "O4") (pin "A") (pinfunction "Anode_A") (pintype "passive"))
      (node (ref "O4") (pin "C") (pinfunction "Coll_C") (pintype "passive"))
      (node (ref "O5") (pin "A") (pinfunction "Anode_A") (pintype "passive"))
      (node (ref "O5") (pin "C") (pinfunction "Coll_C") (pintype "passive"))
      (node (ref "O6") (pin "A") (pinfunction "Anode_A") (pintype "passive"))
      (node (ref "O6") (pin "C") (pinfunction "Coll_C") (pintype "passive"))
      (node (ref "O7") (pin "A") (pinfunction "Anode_A") (pintype "passive"))
      (node (ref "O7") (pin "C") (pinfunction "Coll_C") (pintype "passive"))
      (node (ref "O8") (pin "A") (pinfunction "Anode_A") (pintype "passive"))
      (node (ref "O8") (pin "C") (pinfunction "Coll_C") (pintype "passive"))
      (node (ref "O9") (pin "A") (pinfunction "Anode_A") (pintype "passive"))
      (node (ref "O9") (pin "C") (pinfunction "Coll_C") (pintype "passive"))
      (node (ref "P1") (pin "1") (pinfunction "3V3_1") (pintype "power_in"))
      (node (ref "U1") (pin "24") (pinfunction "VDD_24") (pintype "power_in"))
      (node (ref "U2") (pin "17") (pinfunction "VDRIVE_17") (pintype "power_in"))
      (node (ref "U4") (pin "24") (pinfunction "VDD_24") (pintype "power_in"))
      (node (ref "U5") (pin "17") (pinfunction "VDRIVE_17") (pintype "power_in"))
    )
    (net (code "75") (name "5V") (class "Default")
      (node (ref "C2") (pin "2") (pinfunction "2_2") (pintype "passive"))
      (node (ref "C3") (pin "2") (pinfunction "2_2") (pintype "passive"))
      (node (ref "C6") (pin "2") (pinfunction "2_2") (pintype "passive"))
      (node (ref "C7") (pin "2") (pinfunction "2_2") (pintype "passive"))
      (node (ref "P2") (pin "1") (pinfunction "5V_1") (pintype "power_in"))
      (node (ref "U2") (pin "22") (pinfunction "VDD_22") (pintype "power_in"))
      (node (ref "U3") (pin "2") (pinfunction "VIN_2") (pintype "power_in"))
      (node (ref "U5") (pin "22") (pinfunction "VDD_22") (pintype "power_in"))
      (node (ref "U6") (pin "2") (pinfunction "VIN_2") (pintype "power_in"))
    )
    (net (code "76") (name "GND") (class "Default")
      (node (ref "C1") (pin "1") (pinfunction "1_1") (pintype "passive"))
      (node (ref "C2") (pin "1") (pinfunction "1_1") (pintype "passive"))
      (node (ref "C3") (pin "1") (pinfunction "1_1") (pintype "passive"))
      (node (ref "C4") (pin "1") (pinfunction "1_1") (pintype "passive"))
      (node (ref "C5") (pin "1") (pinfunction "1_1") (pintype "passive"))
      (node (ref "C6") (pin "1") (pinfunction "1_1") (pintype "passive"))
      (node (ref "C7") (pin "1") (pinfunction "1_1") (pintype "passive"))
      (node (ref "C8") (pin "1") (pinfunction "1_1") (pintype "passive"))
      (node (ref "P1") (pin "8") (pinfunction "GND_8") (pintype "power_in"))
      (node (ref "P2") (pin "5") (pinfunction "GND_5") (pintype "power_in"))
      (node (ref "R1") (pin "2") (pinfunction "2_2") (pintype "passive"))
      (node (ref "R10") (pin "1") (pinfunction "1_1") (pintype "passive"))
      (node (ref "R11") (pin "1") (pinfunction "1_1") (pintype "passive"))
      (node (ref "R12") (pin "1") (pinfunction "1_1") (pintype "passive"))
      (node (ref "R13") (pin "1") (pinfunction "1_1") (pintype "passive"))
      (node (ref "R14") (pin "1") (pinfunction "1_1") (pintype "passive"))
      (node (ref "R15") (pin "1") (pinfunction "1_1") (pintype "passive"))
      (node (ref "R16") (pin "1") (pinfunction "1_1") (pintype "passive"))
      (node (ref "R17") (pin "2") (pinfunction "2_2") (pintype "passive"))
      (node (ref "R18") (pin "1") (pinfunction "1_1") (pintype "passive"))
      (node (ref "R19") (pin "1") (pinfunction "1_1") (pintype "passive"))
      (node (ref "R2") (pin "1") (pinfunction "1_1") (pintype "passive"))
      (node (ref "R20") (pin "1") (pinfunction "1_1") (pintype "passive"))
      (node (ref "R21") (pin "1") (pinfunction "1_1") (pintype "passive"))
      (node (ref "R22") (pin "1") (pinfunction "1_1") (pintype "passive"))
      (node (ref "R23") (pin "1") (pinfunction "1_1") (pintype "passive"))
      (node (ref "R24") (pin "1") (pinfunction "1_1") (pintype "passive"))
      (node (ref "R25") (pin "1") (pinfunction "1_1") (pintype "passive"))
      (node (ref "R26") (pin "1") (pinfunction "1_1") (pintype "passive"))
      (node (ref "R27") (pin "1") (pinfunction "1_1") (pintype "passive"))
      (node (ref "R28") (pin "1") (pinfunction "1_1") (pintype "passive"))
      (node (ref "R29") (pin "1") (pinfunction "1_1") (pintype "passive"))
      (node (ref "R3") (pin "1") (pinfunction "1_1") (pintype "passive"))
      (node (ref "R30") (pin "1") (pinfunction "1_1") (pintype "passive"))
      (node (ref "R31") (pin "1") (pinfunction "1_1") (pintype "passive"))
      (node (ref "R32") (pin "1") (pinfunction "1_1") (pintype "passive"))
      (node (ref "R4") (pin "1") (pinfunction "1_1") (pintype "passive"))
      (node (ref "R5") (pin "1") (pinfunction "1_1") (pintype "passive"))
      (node (ref "R6") (pin "1") (pinfunction "1_1") (pintype "passive"))
      (node (ref "R7") (pin "1") (pinfunction "1_1") (pintype "passive"))
      (node (ref "R8") (pin "1") (pinfunction "1_1") (pintype "passive"))
      (node (ref "R9") (pin "1") (pinfunction "1_1") (pintype "passive"))
      (node (ref "R_EXT1") (pin "1") (pinfunction "1_1") (pintype "passive"))
      (node (ref "R_EXT2") (pin "1") (pinfunction "1_1") (pintype "passive"))
      (node (ref "U1") (pin "1") (pinfunction "GND_1") (pintype "power_in"))
      (node (ref "U2") (pin "14") (pinfunction "AGND_14") (pintype "power_in"))
      (node (ref "U2") (pin "18") (pinfunction "NC_18") (pintype "power_in"))
      (node (ref "U2") (pin "21") (pinfunction "AGND_21") (pintype "power_in"))
      (node (ref "U2") (pin "24") (pinfunction "AGND_24") (pintype "power_in"))
      (node (ref "U2") (pin "4") (pinfunction "NC_4") (pintype "power_in"))
      (node (ref "U3") (pin "4") (pinfunction "GND_4") (pintype "power_in"))
      (node (ref "U4") (pin "1") (pinfunction "GND_1") (pintype "power_in"))
      (node (ref "U5") (pin "14") (pinfunction "AGND_14") (pintype "power_in"))
      (node (ref "U5") (pin "18") (pinfunction "NC_18") (pintype "power_in"))
      (node (ref "U5") (pin "21") (pinfunction "AGND_21") (pintype "power_in"))
      (node (ref "U5") (pin "24") (pinfunction "AGND_24") (pintype "power_in"))
      (node (ref "U5") (pin "4") (pinfunction "NC_4") (pintype "power_in"))
      (node (ref "U6") (pin "4") (pinfunction "GND_4") (pintype "power_in"))
    )
    (net (code "77") (name "Net-(P1-~{LE})") (class "Default")
      (node (ref "P1") (pin "7") (pinfunction "~{LE}_7") (pintype "output"))
      (node (ref "U1") (pin "4") (pinfunction "LE_4") (pintype "input"))
    )
    (net (code "78") (name "Net-(P1-~{OE})") (class "Default")
      (node (ref "P1") (pin "6") (pinfunction "~{OE}_6") (pintype "output"))
      (node (ref "U1") (pin "21") (pinfunction "~{OE}_21") (pintype "input"))
    )
    (net (code "79") (name "Net-(P2-~{LE})") (class "Default")
      (node (ref "P2") (pin "4") (pinfunction "~{LE}_4") (pintype "output"))
      (node (ref "U4") (pin "4") (pinfunction "LE_4") (pintype "input"))
    )
    (net (code "80") (name "Net-(P2-~{OE})") (class "Default")
      (node (ref "P2") (pin "3") (pinfunction "~{OE}_3") (pintype "output"))
      (node (ref "U4") (pin "21") (pinfunction "~{OE}_21") (pintype "input"))
    )
    (net (code "81") (name "Net-(U1-R-EXT)") (class "Default")
      (node (ref "R_EXT1") (pin "2") (pinfunction "2_2") (pintype "passive"))
      (node (ref "U1") (pin "23") (pinfunction "R-EXT_23") (pintype "passive"))
    )
    (net (code "82") (name "Net-(U2-REFIN)") (class "Default")
      (node (ref "C4") (pin "2") (pinfunction "2_2") (pintype "passive"))
      (node (ref "U2") (pin "23") (pinfunction "REFIN_23") (pintype "power_in"))
      (node (ref "U3") (pin "6") (pinfunction "VOUT_6") (pintype "power_in"))
    )
    (net (code "83") (name "Net-(U4-R-EXT)") (class "Default")
      (node (ref "R_EXT2") (pin "2") (pinfunction "2_2") (pintype "passive"))
      (node (ref "U4") (pin "23") (pinfunction "R-EXT_23") (pintype "passive"))
    )
    (net (code "84") (name "Net-(U5-REFIN)") (class "Default")
      (node (ref "C8") (pin "2") (pinfunction "2_2") (pintype "passive"))
      (node (ref "U5") (pin "23") (pinfunction "REFIN_23") (pintype "power_in"))
      (node (ref "U6") (pin "6") (pinfunction "VOUT_6") (pintype "power_in"))
    )
    (net (code "85") (name "unconnected-(U3-NIC-Pad3)") (class "Default")
      (node (ref "U3") (pin "3") (pinfunction "NIC_3") (pintype "passive"))
    )
    (net (code "86") (name "unconnected-(U3-NIC-Pad7)") (class "Default")
      (node (ref "U3") (pin "7") (pinfunction "NIC_7") (pintype "passive"))
    )
    (net (code "87") (name "unconnected-(U3-TP-Pad1)") (class "Default")
      (node (ref "U3") (pin "1") (pinfunction "TP_1") (pintype "passive"))
    )
    (net (code "88") (name "unconnected-(U3-TP-Pad8)") (class "Default")
      (node (ref "U3") (pin "8") (pinfunction "TP_8") (pintype "passive"))
    )
    (net (code "89") (name "unconnected-(U3-TRIM-Pad5)") (class "Default")
      (node (ref "U3") (pin "5") (pinfunction "TRIM_5") (pintype "passive"))
    )
    (net (code "90") (name "unconnected-(U6-NIC-Pad3)") (class "Default")
      (node (ref "U6") (pin "3") (pinfunction "NIC_3") (pintype "passive"))
    )
    (net (code "91") (name "unconnected-(U6-NIC-Pad7)") (class "Default")
      (node (ref "U6") (pin "7") (pinfunction "NIC_7") (pintype "passive"))
    )
    (net (code "92") (name "unconnected-(U6-TP-Pad1)") (class "Default")
      (node (ref "U6") (pin "1") (pinfunction "TP_1") (pintype "passive"))
    )
    (net (code "93") (name "unconnected-(U6-TP-Pad8)") (class "Default")
      (node (ref "U6") (pin "8") (pinfunction "TP_8") (pintype "passive"))
    )
    (net (code "94") (name "unconnected-(U6-TRIM-Pad5)") (class "Default")
      (node (ref "U6") (pin "5") (pinfunction "TRIM_5") (pintype "passive"))
    )
  )
)
